# crosstalk-4.net
KiCad netlist of a schematic drawn in Altium Designer
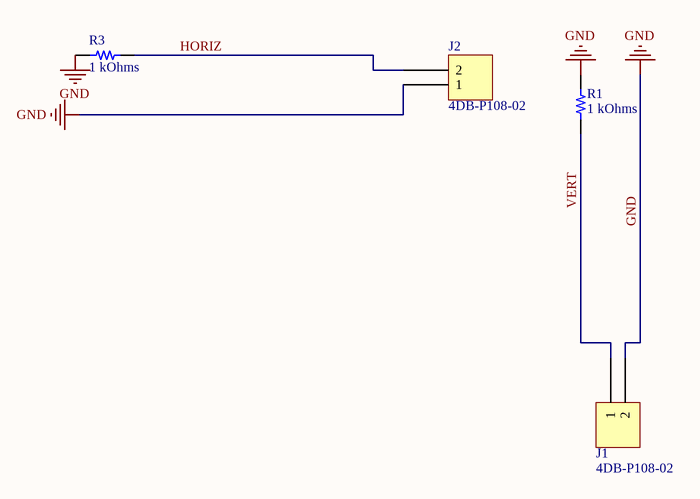
[diagram p0: crosstalk-4.SchDoc]

(export (version "E")
  (design (tool "Eeschema 10.0.6"))
  (components
    (comp (ref "J1")
      (value "4DB-P108-02")
      (footprint "TE 4DB-P108-02")
      (description "CONN BARRIER STRIP 2CIRC 0.325\"")
      (fields (field (name "MANUFACTURER") "TE Connectivity AMP Connectors"))
      (libsource (lib "Celestial Altium Library - altium_library") (part "2 Pin"))
    )
    (comp (ref "J2")
      (value "4DB-P108-02")
      (footprint "TE 4DB-P108-02")
      (description "CONN BARRIER STRIP 2CIRC 0.325\"")
      (fields (field (name "MANUFACTURER") "TE Connectivity AMP Connectors"))
      (libsource (lib "") (part "2 Pin_1"))
    )
    (comp (ref "R1")
      (value "1 kOhms")
      (footprint "RES 0603_1608")
      (description "RES SMD 1K OHM 0.1% 1/16W 0603")
      (fields
        (field (name "PART NUMBER") "CPF0603B1K0E")
        (field (name "MANUFACTURER") "TE Connectivity Passive Product")
      )
      (libsource (lib "Celestial Altium Library - altium_library") (part "Resistor"))
    )
    (comp (ref "R3")
      (value "1 kOhms")
      (footprint "RES 0603_1608")
      (description "RES SMD 1K OHM 0.1% 1/16W 0603")
      (fields
        (field (name "PART NUMBER") "CPF0603B1K0E")
        (field (name "MANUFACTURER") "TE Connectivity Passive Product")
      )
      (libsource (lib "Celestial Altium Library - altium_library") (part "Resistor"))
    )
  )
  (nets
    (net (code "1") (name "/HORIZ") (class "Default")
      (node (ref "J2") (pin "2") (pinfunction "2_2") (pintype "passive"))
      (node (ref "R3") (pin "1") (pinfunction "1_1") (pintype "passive"))
    )
    (net (code "2") (name "/VERT") (class "Default")
      (node (ref "J1") (pin "1") (pinfunction "1_1") (pintype "passive"))
      (node (ref "R1") (pin "1") (pinfunction "1_1") (pintype "passive"))
    )
    (net (code "3") (name "GND") (class "Default")
      (node (ref "J1") (pin "2") (pinfunction "2_2") (pintype "passive"))
      (node (ref "J2") (pin "1") (pinfunction "1_1") (pintype "passive"))
      (node (ref "R1") (pin "2") (pinfunction "2_2") (pintype "passive"))
      (node (ref "R3") (pin "2") (pinfunction "2_2") (pintype "passive"))
    )
  )
)
